# DeejBusinessCard-LEDs.net
KiCad netlist of a schematic drawn in Altium Designer
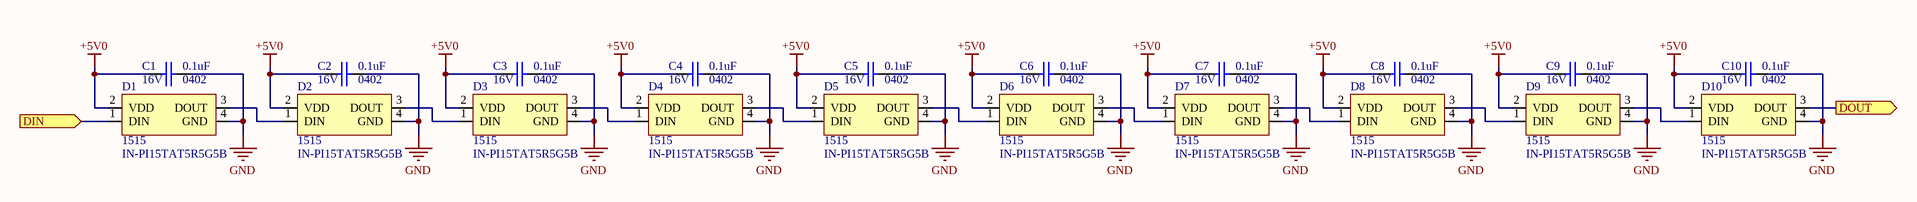
[diagram p0: DeejBusinessCard-LEDs.SchDoc]

(export (version "E")
  (design (tool "Eeschema 10.0.6"))
  (components
    (comp (ref "C1")
      (value "0.1uF")
      (footprint "CAPC1005L")
      (description "CAP CER 0.1UF 16V X7R 0402")
      (fields
        (field (name "CASE/PACKAGE") "0402")
        (field (name "VOLTAGE") "16V")
        (field (name "PART NUMBER") "CC0402KRX7R7BB104")
        (field (name "Comment") "Capacitor_Ceramic")
      )
      (libsource (lib "Capacitors") (part "Capacitor_Ceramic"))
    )
    (comp (ref "C2")
      (value "0.1uF")
      (footprint "CAPC1005L")
      (description "CAP CER 0.1UF 16V X7R 0402")
      (fields
        (field (name "CASE/PACKAGE") "0402")
        (field (name "VOLTAGE") "16V")
        (field (name "PART NUMBER") "CC0402KRX7R7BB104")
        (field (name "Comment") "Capacitor_Ceramic")
      )
      (libsource (lib "Capacitors") (part "Capacitor_Ceramic"))
    )
    (comp (ref "C3")
      (value "0.1uF")
      (footprint "CAPC1005L")
      (description "CAP CER 0.1UF 16V X7R 0402")
      (fields
        (field (name "CASE/PACKAGE") "0402")
        (field (name "VOLTAGE") "16V")
        (field (name "PART NUMBER") "CC0402KRX7R7BB104")
        (field (name "Comment") "Capacitor_Ceramic")
      )
      (libsource (lib "Capacitors") (part "Capacitor_Ceramic"))
    )
    (comp (ref "C4")
      (value "0.1uF")
      (footprint "CAPC1005L")
      (description "CAP CER 0.1UF 16V X7R 0402")
      (fields
        (field (name "CASE/PACKAGE") "0402")
        (field (name "VOLTAGE") "16V")
        (field (name "PART NUMBER") "CC0402KRX7R7BB104")
        (field (name "Comment") "Capacitor_Ceramic")
      )
      (libsource (lib "Capacitors") (part "Capacitor_Ceramic"))
    )
    (comp (ref "C5")
      (value "0.1uF")
      (footprint "CAPC1005L")
      (description "CAP CER 0.1UF 16V X7R 0402")
      (fields
        (field (name "CASE/PACKAGE") "0402")
        (field (name "VOLTAGE") "16V")
        (field (name "PART NUMBER") "CC0402KRX7R7BB104")
        (field (name "Comment") "Capacitor_Ceramic")
      )
      (libsource (lib "Capacitors") (part "Capacitor_Ceramic"))
    )
    (comp (ref "C6")
      (value "0.1uF")
      (footprint "CAPC1005L")
      (description "CAP CER 0.1UF 16V X7R 0402")
      (fields
        (field (name "CASE/PACKAGE") "0402")
        (field (name "VOLTAGE") "16V")
        (field (name "PART NUMBER") "CC0402KRX7R7BB104")
        (field (name "Comment") "Capacitor_Ceramic")
      )
      (libsource (lib "Capacitors") (part "Capacitor_Ceramic"))
    )
    (comp (ref "C7")
      (value "0.1uF")
      (footprint "CAPC1005L")
      (description "CAP CER 0.1UF 16V X7R 0402")
      (fields
        (field (name "CASE/PACKAGE") "0402")
        (field (name "VOLTAGE") "16V")
        (field (name "PART NUMBER") "CC0402KRX7R7BB104")
        (field (name "Comment") "Capacitor_Ceramic")
      )
      (libsource (lib "Capacitors") (part "Capacitor_Ceramic"))
    )
    (comp (ref "C8")
      (value "0.1uF")
      (footprint "CAPC1005L")
      (description "CAP CER 0.1UF 16V X7R 0402")
      (fields
        (field (name "CASE/PACKAGE") "0402")
        (field (name "VOLTAGE") "16V")
        (field (name "PART NUMBER") "CC0402KRX7R7BB104")
        (field (name "Comment") "Capacitor_Ceramic")
      )
      (libsource (lib "Capacitors") (part "Capacitor_Ceramic"))
    )
    (comp (ref "C9")
      (value "0.1uF")
      (footprint "CAPC1005L")
      (description "CAP CER 0.1UF 16V X7R 0402")
      (fields
        (field (name "CASE/PACKAGE") "0402")
        (field (name "VOLTAGE") "16V")
        (field (name "PART NUMBER") "CC0402KRX7R7BB104")
        (field (name "Comment") "Capacitor_Ceramic")
      )
      (libsource (lib "Capacitors") (part "Capacitor_Ceramic"))
    )
    (comp (ref "C10")
      (value "0.1uF")
      (footprint "CAPC1005L")
      (description "CAP CER 0.1UF 16V X7R 0402")
      (fields
        (field (name "CASE/PACKAGE") "0402")
        (field (name "VOLTAGE") "16V")
        (field (name "PART NUMBER") "CC0402KRX7R7BB104")
        (field (name "Comment") "Capacitor_Ceramic")
      )
      (libsource (lib "Capacitors") (part "Capacitor_Ceramic"))
    )
    (comp (ref "D1")
      (value "IN-PI15TAT5R5G5B")
      (footprint "IN-PI15TAT5R5G5B")
      (description "Addressable Lighting - 1 LED Discrete Red, Green, Blue (RGB) 1.50mm L x 1.50mm W")
      (fields
        (field (name "MANUFACTURER") "Inolux")
        (field (name "PCB FOOTPRINT") "1515")
        (field (name "PART NUMBER") "IN-PI15TAT5R5G5B")
      )
      (libsource (lib "42e-SharedLib") (part "IN-PI15TAT5R5G5B"))
    )
    (comp (ref "D2")
      (value "IN-PI15TAT5R5G5B")
      (footprint "IN-PI15TAT5R5G5B")
      (description "Addressable Lighting - 1 LED Discrete Red, Green, Blue (RGB) 1.50mm L x 1.50mm W")
      (fields
        (field (name "MANUFACTURER") "Inolux")
        (field (name "PCB FOOTPRINT") "1515")
        (field (name "PART NUMBER") "IN-PI15TAT5R5G5B")
      )
      (libsource (lib "42e-SharedLib") (part "IN-PI15TAT5R5G5B"))
    )
    (comp (ref "D3")
      (value "IN-PI15TAT5R5G5B")
      (footprint "IN-PI15TAT5R5G5B")
      (description "Addressable Lighting - 1 LED Discrete Red, Green, Blue (RGB) 1.50mm L x 1.50mm W")
      (fields
        (field (name "MANUFACTURER") "Inolux")
        (field (name "PCB FOOTPRINT") "1515")
        (field (name "PART NUMBER") "IN-PI15TAT5R5G5B")
      )
      (libsource (lib "42e-SharedLib") (part "IN-PI15TAT5R5G5B"))
    )
    (comp (ref "D4")
      (value "IN-PI15TAT5R5G5B")
      (footprint "IN-PI15TAT5R5G5B")
      (description "Addressable Lighting - 1 LED Discrete Red, Green, Blue (RGB) 1.50mm L x 1.50mm W")
      (fields
        (field (name "MANUFACTURER") "Inolux")
        (field (name "PCB FOOTPRINT") "1515")
        (field (name "PART NUMBER") "IN-PI15TAT5R5G5B")
      )
      (libsource (lib "42e-SharedLib") (part "IN-PI15TAT5R5G5B"))
    )
    (comp (ref "D5")
      (value "IN-PI15TAT5R5G5B")
      (footprint "IN-PI15TAT5R5G5B")
      (description "Addressable Lighting - 1 LED Discrete Red, Green, Blue (RGB) 1.50mm L x 1.50mm W")
      (fields
        (field (name "MANUFACTURER") "Inolux")
        (field (name "PCB FOOTPRINT") "1515")
        (field (name "PART NUMBER") "IN-PI15TAT5R5G5B")
      )
      (libsource (lib "42e-SharedLib") (part "IN-PI15TAT5R5G5B"))
    )
    (comp (ref "D6")
      (value "IN-PI15TAT5R5G5B")
      (footprint "IN-PI15TAT5R5G5B")
      (description "Addressable Lighting - 1 LED Discrete Red, Green, Blue (RGB) 1.50mm L x 1.50mm W")
      (fields
        (field (name "MANUFACTURER") "Inolux")
        (field (name "PCB FOOTPRINT") "1515")
        (field (name "PART NUMBER") "IN-PI15TAT5R5G5B")
      )
      (libsource (lib "42e-SharedLib") (part "IN-PI15TAT5R5G5B"))
    )
    (comp (ref "D7")
      (value "IN-PI15TAT5R5G5B")
      (footprint "IN-PI15TAT5R5G5B")
      (description "Addressable Lighting - 1 LED Discrete Red, Green, Blue (RGB) 1.50mm L x 1.50mm W")
      (fields
        (field (name "MANUFACTURER") "Inolux")
        (field (name "PCB FOOTPRINT") "1515")
        (field (name "PART NUMBER") "IN-PI15TAT5R5G5B")
      )
      (libsource (lib "42e-SharedLib") (part "IN-PI15TAT5R5G5B"))
    )
    (comp (ref "D8")
      (value "IN-PI15TAT5R5G5B")
      (footprint "IN-PI15TAT5R5G5B")
      (description "Addressable Lighting - 1 LED Discrete Red, Green, Blue (RGB) 1.50mm L x 1.50mm W")
      (fields
        (field (name "MANUFACTURER") "Inolux")
        (field (name "PCB FOOTPRINT") "1515")
        (field (name "PART NUMBER") "IN-PI15TAT5R5G5B")
      )
      (libsource (lib "42e-SharedLib") (part "IN-PI15TAT5R5G5B"))
    )
    (comp (ref "D9")
      (value "IN-PI15TAT5R5G5B")
      (footprint "IN-PI15TAT5R5G5B")
      (description "Addressable Lighting - 1 LED Discrete Red, Green, Blue (RGB) 1.50mm L x 1.50mm W")
      (fields
        (field (name "MANUFACTURER") "Inolux")
        (field (name "PCB FOOTPRINT") "1515")
        (field (name "PART NUMBER") "IN-PI15TAT5R5G5B")
      )
      (libsource (lib "42e-SharedLib") (part "IN-PI15TAT5R5G5B"))
    )
    (comp (ref "D10")
      (value "IN-PI15TAT5R5G5B")
      (footprint "IN-PI15TAT5R5G5B")
      (description "Addressable Lighting - 1 LED Discrete Red, Green, Blue (RGB) 1.50mm L x 1.50mm W")
      (fields
        (field (name "MANUFACTURER") "Inolux")
        (field (name "PCB FOOTPRINT") "1515")
        (field (name "PART NUMBER") "IN-PI15TAT5R5G5B")
      )
      (libsource (lib "42e-SharedLib") (part "IN-PI15TAT5R5G5B"))
    )
  )
  (nets
    (net (code "1") (name "+5V0") (class "Default")
      (node (ref "C1") (pin "2") (pinfunction "2_2") (pintype "passive"))
      (node (ref "C10") (pin "2") (pinfunction "2_2") (pintype "passive"))
      (node (ref "C2") (pin "2") (pinfunction "2_2") (pintype "passive"))
      (node (ref "C3") (pin "2") (pinfunction "2_2") (pintype "passive"))
      (node (ref "C4") (pin "2") (pinfunction "2_2") (pintype "passive"))
      (node (ref "C5") (pin "2") (pinfunction "2_2") (pintype "passive"))
      (node (ref "C6") (pin "2") (pinfunction "2_2") (pintype "passive"))
      (node (ref "C7") (pin "2") (pinfunction "2_2") (pintype "passive"))
      (node (ref "C8") (pin "2") (pinfunction "2_2") (pintype "passive"))
      (node (ref "C9") (pin "2") (pinfunction "2_2") (pintype "passive"))
      (node (ref "D1") (pin "2") (pinfunction "VDD_2") (pintype "passive"))
      (node (ref "D10") (pin "2") (pinfunction "VDD_2") (pintype "passive"))
      (node (ref "D2") (pin "2") (pinfunction "VDD_2") (pintype "passive"))
      (node (ref "D3") (pin "2") (pinfunction "VDD_2") (pintype "passive"))
      (node (ref "D4") (pin "2") (pinfunction "VDD_2") (pintype "passive"))
      (node (ref "D5") (pin "2") (pinfunction "VDD_2") (pintype "passive"))
      (node (ref "D6") (pin "2") (pinfunction "VDD_2") (pintype "passive"))
      (node (ref "D7") (pin "2") (pinfunction "VDD_2") (pintype "passive"))
      (node (ref "D8") (pin "2") (pinfunction "VDD_2") (pintype "passive"))
      (node (ref "D9") (pin "2") (pinfunction "VDD_2") (pintype "passive"))
    )
    (net (code "2") (name "/DIN") (class "Default")
      (node (ref "D1") (pin "1") (pinfunction "DIN_1") (pintype "passive"))
    )
    (net (code "3") (name "/DOUT") (class "Default")
      (node (ref "D10") (pin "3") (pinfunction "DOUT_3") (pintype "passive"))
    )
    (net (code "4") (name "GND") (class "Default")
      (node (ref "C1") (pin "1") (pinfunction "1_1") (pintype "passive"))
      (node (ref "C10") (pin "1") (pinfunction "1_1") (pintype "passive"))
      (node (ref "C2") (pin "1") (pinfunction "1_1") (pintype "passive"))
      (node (ref "C3") (pin "1") (pinfunction "1_1") (pintype "passive"))
      (node (ref "C4") (pin "1") (pinfunction "1_1") (pintype "passive"))
      (node (ref "C5") (pin "1") (pinfunction "1_1") (pintype "passive"))
      (node (ref "C6") (pin "1") (pinfunction "1_1") (pintype "passive"))
      (node (ref "C7") (pin "1") (pinfunction "1_1") (pintype "passive"))
      (node (ref "C8") (pin "1") (pinfunction "1_1") (pintype "passive"))
      (node (ref "C9") (pin "1") (pinfunction "1_1") (pintype "passive"))
      (node (ref "D1") (pin "4") (pinfunction "GND_4") (pintype "passive"))
      (node (ref "D10") (pin "4") (pinfunction "GND_4") (pintype "passive"))
      (node (ref "D2") (pin "4") (pinfunction "GND_4") (pintype "passive"))
      (node (ref "D3") (pin "4") (pinfunction "GND_4") (pintype "passive"))
      (node (ref "D4") (pin "4") (pinfunction "GND_4") (pintype "passive"))
      (node (ref "D5") (pin "4") (pinfunction "GND_4") (pintype "passive"))
      (node (ref "D6") (pin "4") (pinfunction "GND_4") (pintype "passive"))
      (node (ref "D7") (pin "4") (pinfunction "GND_4") (pintype "passive"))
      (node (ref "D8") (pin "4") (pinfunction "GND_4") (pintype "passive"))
      (node (ref "D9") (pin "4") (pinfunction "GND_4") (pintype "passive"))
    )
    (net (code "5") (name "Net-(D1-DOUT)") (class "Default")
      (node (ref "D1") (pin "3") (pinfunction "DOUT_3") (pintype "passive"))
      (node (ref "D2") (pin "1") (pinfunction "DIN_1") (pintype "passive"))
    )
    (net (code "6") (name "Net-(D2-DOUT)") (class "Default")
      (node (ref "D2") (pin "3") (pinfunction "DOUT_3") (pintype "passive"))
      (node (ref "D3") (pin "1") (pinfunction "DIN_1") (pintype "passive"))
    )
    (net (code "7") (name "Net-(D3-DOUT)") (class "Default")
      (node (ref "D3") (pin "3") (pinfunction "DOUT_3") (pintype "passive"))
      (node (ref "D4") (pin "1") (pinfunction "DIN_1") (pintype "passive"))
    )
    (net (code "8") (name "Net-(D4-DOUT)") (class "Default")
      (node (ref "D4") (pin "3") (pinfunction "DOUT_3") (pintype "passive"))
      (node (ref "D5") (pin "1") (pinfunction "DIN_1") (pintype "passive"))
    )
    (net (code "9") (name "Net-(D5-DOUT)") (class "Default")
      (node (ref "D5") (pin "3") (pinfunction "DOUT_3") (pintype "passive"))
      (node (ref "D6") (pin "1") (pinfunction "DIN_1") (pintype "passive"))
    )
    (net (code "10") (name "Net-(D6-DOUT)") (class "Default")
      (node (ref "D6") (pin "3") (pinfunction "DOUT_3") (pintype "passive"))
      (node (ref "D7") (pin "1") (pinfunction "DIN_1") (pintype "passive"))
    )
    (net (code "11") (name "Net-(D7-DOUT)") (class "Default")
      (node (ref "D7") (pin "3") (pinfunction "DOUT_3") (pintype "passive"))
      (node (ref "D8") (pin "1") (pinfunction "DIN_1") (pintype "passive"))
    )
    (net (code "12") (name "Net-(D8-DOUT)") (class "Default")
      (node (ref "D8") (pin "3") (pinfunction "DOUT_3") (pintype "passive"))
      (node (ref "D9") (pin "1") (pinfunction "DIN_1") (pintype "passive"))
    )
    (net (code "13") (name "Net-(D10-DIN)") (class "Default")
      (node (ref "D10") (pin "1") (pinfunction "DIN_1") (pintype "passive"))
      (node (ref "D9") (pin "3") (pinfunction "DOUT_3") (pintype "passive"))
    )
  )
)
